# micro_RevA.net
KiCad netlist of a schematic drawn in EAGLE
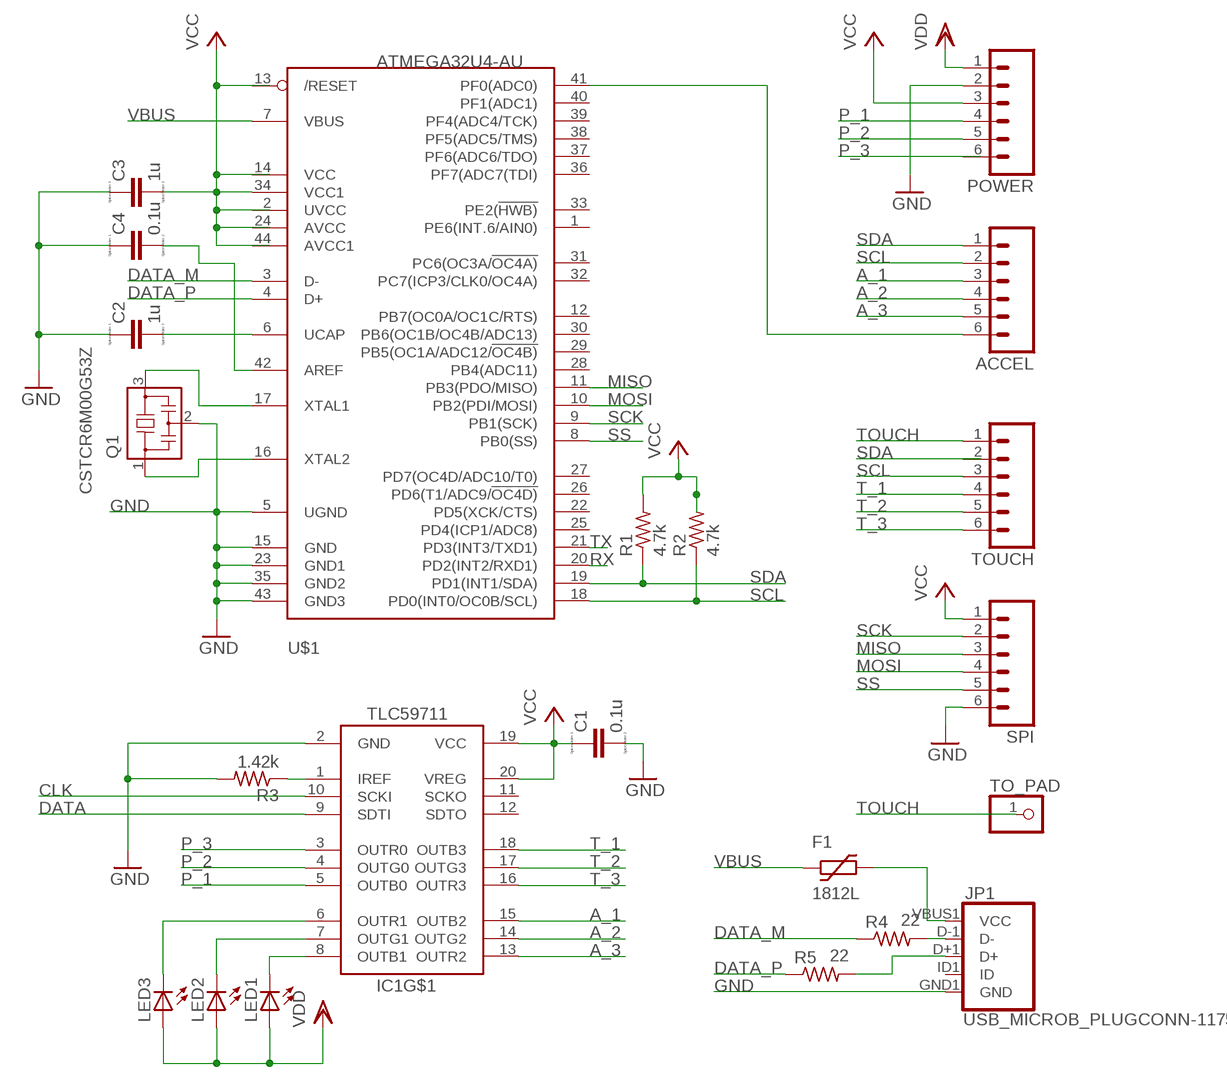
[diagram p0: schematic, sheet 1]

(export (version "E")
  (design (tool "Eeschema 10.0.6"))
  (components
    (comp (ref "ACCEL")
      (value "M06SMD-STRAIGHT-ALT")
      (footprint "eagle-import:1X06_SMD_STRAIGHT_ALT")
      (libsource (lib "eagle-import") (part "M06SMD-STRAIGHT-ALT"))
    )
    (comp (ref "C1")
      (value "0.1u")
      (footprint "eagle-import:C0603")
      (libsource (lib "eagle-import") (part "CC0603"))
    )
    (comp (ref "C2")
      (value "1u")
      (footprint "eagle-import:C0603")
      (libsource (lib "eagle-import") (part "CC0603"))
    )
    (comp (ref "C3")
      (value "1u")
      (footprint "eagle-import:C0603")
      (libsource (lib "eagle-import") (part "CC0603"))
    )
    (comp (ref "C4")
      (value "0.1u")
      (footprint "eagle-import:C0603")
      (libsource (lib "eagle-import") (part "CC0603"))
    )
    (comp (ref "F1")
      (value "1812L")
      (footprint "eagle-import:1812L")
      (libsource (lib "eagle-import") (part "1812L"))
    )
    (comp (ref "IC1")
      (value "TLC59711")
      (footprint "eagle-import:HTSSOP20DAP")
      (libsource (lib "eagle-import") (part "TLC59711"))
    )
    (comp (ref "JP1")
      (value "USB_MICROB_PLUGCONN-11752")
      (footprint "eagle-import:USB-B-MICRO-SMD_V03")
      (libsource (lib "eagle-import") (part "USB_MICROB_PLUGCONN-11752"))
    )
    (comp (ref "LED1")
      (value "LEDP-LCC-4")
      (footprint "eagle-import:P-LCC-4")
      (libsource (lib "eagle-import") (part "LEDP-LCC-4"))
    )
    (comp (ref "LED2")
      (value "LEDP-LCC-4")
      (footprint "eagle-import:P-LCC-4")
      (libsource (lib "eagle-import") (part "LEDP-LCC-4"))
    )
    (comp (ref "LED3")
      (value "LEDP-LCC-4")
      (footprint "eagle-import:P-LCC-4")
      (libsource (lib "eagle-import") (part "LEDP-LCC-4"))
    )
    (comp (ref "POWER")
      (value "M06SMD-STRAIGHT-ALT")
      (footprint "eagle-import:1X06_SMD_STRAIGHT_ALT")
      (libsource (lib "eagle-import") (part "M06SMD-STRAIGHT-ALT"))
    )
    (comp (ref "Q1")
      (value "CSTCR6M00G53Z")
      (footprint "eagle-import:CSTCR6M")
      (fields (field (name "MPN") "CSTCR6M00G53-R0"))
      (libsource (lib "eagle-import") (part "CSTCR6M00G53Z"))
    )
    (comp (ref "R1")
      (value "4.7k")
      (footprint "eagle-import:R0603")
      (libsource (lib "eagle-import") (part "R-US_R0603"))
    )
    (comp (ref "R2")
      (value "4.7k")
      (footprint "eagle-import:R0603")
      (libsource (lib "eagle-import") (part "R-US_R0603"))
    )
    (comp (ref "R3")
      (value "1.42k")
      (footprint "eagle-import:R0603")
      (libsource (lib "eagle-import") (part "R-US_R0603"))
    )
    (comp (ref "R4")
      (value "22")
      (footprint "eagle-import:R0603")
      (libsource (lib "eagle-import") (part "R-US_R0603"))
    )
    (comp (ref "R5")
      (value "22")
      (footprint "eagle-import:R0603")
      (libsource (lib "eagle-import") (part "R-US_R0603"))
    )
    (comp (ref "SPI")
      (value "M06SMD-STRAIGHT-ALT")
      (footprint "eagle-import:1X06_SMD_STRAIGHT_ALT")
      (libsource (lib "eagle-import") (part "M06SMD-STRAIGHT-ALT"))
    )
    (comp (ref "TOUCH")
      (value "M06SMD-STRAIGHT-ALT")
      (footprint "eagle-import:1X06_SMD_STRAIGHT_ALT")
      (libsource (lib "eagle-import") (part "M06SMD-STRAIGHT-ALT"))
    )
    (comp (ref "TO_PAD")
      (value "PINHD-1X1")
      (footprint "eagle-import:1X01")
      (libsource (lib "eagle-import") (part "PINHD-1X1"))
    )
    (comp (ref "U$1")
      (value "ATMEGA32U4-AU")
      (footprint "eagle-import:TQFP44")
      (libsource (lib "eagle-import") (part "ATMEGA32U4-AU"))
    )
  )
  (nets
    (net (code "1") (name "/A_1") (class "Default")
      (node (ref "ACCEL") (pin "3") (pinfunction "3_3") (pintype "passive"))
      (node (ref "IC1") (pin "15") (pinfunction "OUTB2_15") (pintype "open_collector"))
    )
    (net (code "2") (name "/A_2") (class "Default")
      (node (ref "ACCEL") (pin "4") (pinfunction "4_4") (pintype "passive"))
      (node (ref "IC1") (pin "14") (pinfunction "OUTG2_14") (pintype "open_collector"))
    )
    (net (code "3") (name "/A_3") (class "Default")
      (node (ref "ACCEL") (pin "5") (pinfunction "5_5") (pintype "passive"))
      (node (ref "IC1") (pin "13") (pinfunction "OUTR2_13") (pintype "open_collector"))
    )
    (net (code "4") (name "/CLK") (class "Default")
      (node (ref "IC1") (pin "10") (pinfunction "SCKI_10") (pintype "input"))
    )
    (net (code "5") (name "/DATA") (class "Default")
      (node (ref "IC1") (pin "9") (pinfunction "SDTI_9") (pintype "input"))
    )
    (net (code "6") (name "/DATA_M") (class "Default")
      (node (ref "R4") (pin "1") (pinfunction "1_1") (pintype "passive"))
      (node (ref "U$1") (pin "3") (pinfunction "D-_3") (pintype "bidirectional"))
    )
    (net (code "7") (name "/DATA_P") (class "Default")
      (node (ref "R5") (pin "1") (pinfunction "1_1") (pintype "passive"))
      (node (ref "U$1") (pin "4") (pinfunction "D+_4") (pintype "bidirectional"))
    )
    (net (code "8") (name "/MISO") (class "Default")
      (node (ref "SPI") (pin "3") (pinfunction "3_3") (pintype "passive"))
      (node (ref "U$1") (pin "11") (pinfunction "PB3(PDO/MISO)_11") (pintype "bidirectional"))
    )
    (net (code "9") (name "/MOSI") (class "Default")
      (node (ref "SPI") (pin "4") (pinfunction "4_4") (pintype "passive"))
      (node (ref "U$1") (pin "10") (pinfunction "PB2(PDI/MOSI)_10") (pintype "bidirectional"))
    )
    (net (code "10") (name "/P_1") (class "Default")
      (node (ref "IC1") (pin "5") (pinfunction "OUTB0_5") (pintype "open_collector"))
      (node (ref "POWER") (pin "4") (pinfunction "4_4") (pintype "passive"))
    )
    (net (code "11") (name "/P_2") (class "Default")
      (node (ref "IC1") (pin "4") (pinfunction "OUTG0_4") (pintype "open_collector"))
      (node (ref "POWER") (pin "5") (pinfunction "5_5") (pintype "passive"))
    )
    (net (code "12") (name "/P_3") (class "Default")
      (node (ref "IC1") (pin "3") (pinfunction "OUTR0_3") (pintype "open_collector"))
      (node (ref "POWER") (pin "6") (pinfunction "6_6") (pintype "passive"))
    )
    (net (code "13") (name "/RX") (class "Default")
      (node (ref "U$1") (pin "20") (pinfunction "PD2(INT2/RXD1)_20") (pintype "bidirectional"))
    )
    (net (code "14") (name "/SCK") (class "Default")
      (node (ref "SPI") (pin "2") (pinfunction "2_2") (pintype "passive"))
      (node (ref "U$1") (pin "9") (pinfunction "PB1(SCK)_9") (pintype "bidirectional"))
    )
    (net (code "15") (name "/SCL") (class "Default")
      (node (ref "ACCEL") (pin "2") (pinfunction "2_2") (pintype "passive"))
      (node (ref "R2") (pin "1") (pinfunction "1_1") (pintype "passive"))
      (node (ref "TOUCH") (pin "3") (pinfunction "3_3") (pintype "passive"))
      (node (ref "U$1") (pin "18") (pinfunction "PD0(INT0/OC0B/SCL)_18") (pintype "bidirectional"))
    )
    (net (code "16") (name "/SDA") (class "Default")
      (node (ref "ACCEL") (pin "1") (pinfunction "1_1") (pintype "passive"))
      (node (ref "R1") (pin "1") (pinfunction "1_1") (pintype "passive"))
      (node (ref "TOUCH") (pin "2") (pinfunction "2_2") (pintype "passive"))
      (node (ref "U$1") (pin "19") (pinfunction "PD1(INT1/SDA)_19") (pintype "bidirectional"))
    )
    (net (code "17") (name "/SS") (class "Default")
      (node (ref "SPI") (pin "5") (pinfunction "5_5") (pintype "passive"))
      (node (ref "U$1") (pin "8") (pinfunction "PB0(SS)_8") (pintype "bidirectional"))
    )
    (net (code "18") (name "/TOUCH") (class "Default")
      (node (ref "TOUCH") (pin "1") (pinfunction "1_1") (pintype "passive"))
      (node (ref "TO_PAD") (pin "1") (pinfunction "1_1") (pintype "passive"))
    )
    (net (code "19") (name "/TX") (class "Default")
      (node (ref "U$1") (pin "21") (pinfunction "PD3(INT3/TXD1)_21") (pintype "bidirectional"))
    )
    (net (code "20") (name "/T_1") (class "Default")
      (node (ref "IC1") (pin "18") (pinfunction "OUTB3_18") (pintype "open_collector"))
      (node (ref "TOUCH") (pin "4") (pinfunction "4_4") (pintype "passive"))
    )
    (net (code "21") (name "/T_2") (class "Default")
      (node (ref "IC1") (pin "17") (pinfunction "OUTG3_17") (pintype "open_collector"))
      (node (ref "TOUCH") (pin "5") (pinfunction "5_5") (pintype "passive"))
    )
    (net (code "22") (name "/T_3") (class "Default")
      (node (ref "IC1") (pin "16") (pinfunction "OUTR3_16") (pintype "open_collector"))
      (node (ref "TOUCH") (pin "6") (pinfunction "6_6") (pintype "passive"))
    )
    (net (code "23") (name "/VBUS") (class "Default")
      (node (ref "F1") (pin "P$1") (pinfunction "1_P$1") (pintype "passive"))
      (node (ref "U$1") (pin "7") (pinfunction "VBUS_7") (pintype "bidirectional"))
    )
    (net (code "24") (name "GND") (class "Default")
      (node (ref "C1") (pin "2") (pinfunction "2_2") (pintype "passive"))
      (node (ref "C2") (pin "1") (pinfunction "1_1") (pintype "passive"))
      (node (ref "C3") (pin "1") (pinfunction "1_1") (pintype "passive"))
      (node (ref "C4") (pin "1") (pinfunction "1_1") (pintype "passive"))
      (node (ref "IC1") (pin "2") (pinfunction "GND_2") (pintype "power_in"))
      (node (ref "JP1") (pin "GND1") (pinfunction "GND_GND1") (pintype "bidirectional"))
      (node (ref "POWER") (pin "2") (pinfunction "2_2") (pintype "passive"))
      (node (ref "Q1") (pin "2") (pinfunction "2_2") (pintype "passive"))
      (node (ref "R3") (pin "2") (pinfunction "2_2") (pintype "passive"))
      (node (ref "SPI") (pin "6") (pinfunction "6_6") (pintype "passive"))
      (node (ref "U$1") (pin "15") (pinfunction "GND_15") (pintype "bidirectional"))
      (node (ref "U$1") (pin "23") (pinfunction "GND1_23") (pintype "bidirectional"))
      (node (ref "U$1") (pin "35") (pinfunction "GND2_35") (pintype "bidirectional"))
      (node (ref "U$1") (pin "43") (pinfunction "GND3_43") (pintype "bidirectional"))
      (node (ref "U$1") (pin "5") (pinfunction "UGND_5") (pintype "bidirectional"))
    )
    (net (code "25") (name "Net-(F1-2)") (class "Default")
      (node (ref "F1") (pin "P$2") (pinfunction "2_P$2") (pintype "passive"))
      (node (ref "JP1") (pin "VBUS1") (pinfunction "VCC_VBUS1") (pintype "bidirectional"))
    )
    (net (code "26") (name "Net-(IC1A-IREF)") (class "Default")
      (node (ref "IC1") (pin "1") (pinfunction "IREF_1") (pintype "bidirectional"))
      (node (ref "R3") (pin "1") (pinfunction "1_1") (pintype "passive"))
    )
    (net (code "27") (name "Net-(IC1A-OUTB1)") (class "Default")
      (node (ref "IC1") (pin "8") (pinfunction "OUTB1_8") (pintype "open_collector"))
      (node (ref "LED1") (pin "C@4") (pinfunction "C_C@4") (pintype "passive"))
    )
    (net (code "28") (name "Net-(IC1A-OUTG1)") (class "Default")
      (node (ref "IC1") (pin "7") (pinfunction "OUTG1_7") (pintype "open_collector"))
      (node (ref "LED2") (pin "C@4") (pinfunction "C_C@4") (pintype "passive"))
    )
    (net (code "29") (name "Net-(IC1A-OUTR1)") (class "Default")
      (node (ref "IC1") (pin "6") (pinfunction "OUTR1_6") (pintype "open_collector"))
      (node (ref "LED3") (pin "C@4") (pinfunction "C_C@4") (pintype "passive"))
    )
    (net (code "30") (name "Net-(JP1-D+)") (class "Default")
      (node (ref "JP1") (pin "D+1") (pinfunction "D+_D+1") (pintype "bidirectional"))
      (node (ref "R5") (pin "2") (pinfunction "2_2") (pintype "passive"))
    )
    (net (code "31") (name "Net-(JP1-D-)") (class "Default")
      (node (ref "JP1") (pin "D-1") (pinfunction "D-_D-1") (pintype "bidirectional"))
      (node (ref "R4") (pin "2") (pinfunction "2_2") (pintype "passive"))
    )
    (net (code "32") (name "Net-(U$1-AREF)") (class "Default")
      (node (ref "C4") (pin "2") (pinfunction "2_2") (pintype "passive"))
      (node (ref "U$1") (pin "42") (pinfunction "AREF_42") (pintype "bidirectional"))
    )
    (net (code "33") (name "Net-(U$1-PF0(ADC0))") (class "Default")
      (node (ref "ACCEL") (pin "6") (pinfunction "6_6") (pintype "passive"))
      (node (ref "U$1") (pin "41") (pinfunction "PF0(ADC0)_41") (pintype "bidirectional"))
    )
    (net (code "34") (name "Net-(U$1-UCAP)") (class "Default")
      (node (ref "C2") (pin "2") (pinfunction "2_2") (pintype "passive"))
      (node (ref "U$1") (pin "6") (pinfunction "UCAP_6") (pintype "bidirectional"))
    )
    (net (code "35") (name "Net-(U$1-XTAL1)") (class "Default")
      (node (ref "Q1") (pin "3") (pinfunction "3_3") (pintype "passive"))
      (node (ref "U$1") (pin "17") (pinfunction "XTAL1_17") (pintype "bidirectional"))
    )
    (net (code "36") (name "Net-(U$1-XTAL2)") (class "Default")
      (node (ref "Q1") (pin "1") (pinfunction "1_1") (pintype "passive"))
      (node (ref "U$1") (pin "16") (pinfunction "XTAL2_16") (pintype "bidirectional"))
    )
    (net (code "37") (name "VCC") (class "Default")
      (node (ref "C1") (pin "1") (pinfunction "1_1") (pintype "passive"))
      (node (ref "C3") (pin "2") (pinfunction "2_2") (pintype "passive"))
      (node (ref "IC1") (pin "19") (pinfunction "VCC_19") (pintype "power_in"))
      (node (ref "IC1") (pin "20") (pinfunction "VREG_20") (pintype "bidirectional"))
      (node (ref "POWER") (pin "3") (pinfunction "3_3") (pintype "passive"))
      (node (ref "R1") (pin "2") (pinfunction "2_2") (pintype "passive"))
      (node (ref "R2") (pin "2") (pinfunction "2_2") (pintype "passive"))
      (node (ref "SPI") (pin "1") (pinfunction "1_1") (pintype "passive"))
      (node (ref "U$1") (pin "34") (pinfunction "VCC1_34") (pintype "bidirectional"))
    )
    (net (code "38") (name "VDD") (class "Default")
      (node (ref "LED1") (pin "A") (pinfunction "A_A") (pintype "passive"))
      (node (ref "LED2") (pin "A") (pinfunction "A_A") (pintype "passive"))
      (node (ref "LED3") (pin "A") (pinfunction "A_A") (pintype "passive"))
      (node (ref "POWER") (pin "1") (pinfunction "1_1") (pintype "passive"))
    )
    (net (code "39") (name "unconnected-(IC1A-SCKO-Pad11)") (class "Default")
      (node (ref "IC1") (pin "11") (pinfunction "SCKO_11") (pintype "output"))
    )
    (net (code "40") (name "unconnected-(IC1A-SDTO-Pad12)") (class "Default")
      (node (ref "IC1") (pin "12") (pinfunction "SDTO_12") (pintype "output"))
    )
    (net (code "41") (name "unconnected-(JP1-ID-PadID1)") (class "Default")
      (node (ref "JP1") (pin "ID1") (pinfunction "ID_ID1") (pintype "bidirectional"))
    )
    (net (code "42") (name "unconnected-(U$1-AVCC-Pad24)") (class "Default")
      (node (ref "U$1") (pin "24") (pinfunction "AVCC_24") (pintype "bidirectional"))
    )
    (net (code "43") (name "unconnected-(U$1-AVCC1-Pad44)") (class "Default")
      (node (ref "U$1") (pin "44") (pinfunction "AVCC1_44") (pintype "bidirectional"))
    )
    (net (code "44") (name "unconnected-(U$1-PB4(ADC11)-Pad28)") (class "Default")
      (node (ref "U$1") (pin "28") (pinfunction "PB4(ADC11)_28") (pintype "bidirectional"))
    )
    (net (code "45") (name "unconnected-(U$1-PB5(OC1A{slash}ADC12{slash}~{OC4B})-Pad29)") (class "Default")
      (node (ref "U$1") (pin "29") (pinfunction "PB5(OC1A/ADC12/~{OC4B})_29") (pintype "bidirectional"))
    )
    (net (code "46") (name "unconnected-(U$1-PB6(OC1B{slash}OC4B{slash}ADC13)-Pad30)") (class "Default")
      (node (ref "U$1") (pin "30") (pinfunction "PB6(OC1B/OC4B/ADC13)_30") (pintype "bidirectional"))
    )
    (net (code "47") (name "unconnected-(U$1-PB7(OC0A{slash}OC1C{slash}RTS)-Pad12)") (class "Default")
      (node (ref "U$1") (pin "12") (pinfunction "PB7(OC0A/OC1C/RTS)_12") (pintype "bidirectional"))
    )
    (net (code "48") (name "unconnected-(U$1-PC6(OC3A{slash}~{OC4A})-Pad31)") (class "Default")
      (node (ref "U$1") (pin "31") (pinfunction "PC6(OC3A/~{OC4A})_31") (pintype "bidirectional"))
    )
    (net (code "49") (name "unconnected-(U$1-PC7(ICP3{slash}CLK0{slash}OC4A)-Pad32)") (class "Default")
      (node (ref "U$1") (pin "32") (pinfunction "PC7(ICP3/CLK0/OC4A)_32") (pintype "bidirectional"))
    )
    (net (code "50") (name "unconnected-(U$1-PD4(ICP1{slash}ADC8)-Pad25)") (class "Default")
      (node (ref "U$1") (pin "25") (pinfunction "PD4(ICP1/ADC8)_25") (pintype "bidirectional"))
    )
    (net (code "51") (name "unconnected-(U$1-PD5(XCK{slash}CTS)-Pad22)") (class "Default")
      (node (ref "U$1") (pin "22") (pinfunction "PD5(XCK/CTS)_22") (pintype "bidirectional"))
    )
    (net (code "52") (name "unconnected-(U$1-PD6(T1{slash}ADC9{slash}~{OC4D})-Pad26)") (class "Default")
      (node (ref "U$1") (pin "26") (pinfunction "PD6(T1/ADC9/~{OC4D})_26") (pintype "bidirectional"))
    )
    (net (code "53") (name "unconnected-(U$1-PD7(OC4D{slash}ADC10{slash}T0)-Pad27)") (class "Default")
      (node (ref "U$1") (pin "27") (pinfunction "PD7(OC4D/ADC10/T0)_27") (pintype "bidirectional"))
    )
    (net (code "54") (name "unconnected-(U$1-PE2(~{HWB})-Pad33)") (class "Default")
      (node (ref "U$1") (pin "33") (pinfunction "PE2(~{HWB})_33") (pintype "bidirectional"))
    )
    (net (code "55") (name "unconnected-(U$1-PE6(INT.6{slash}AIN0)-Pad1)") (class "Default")
      (node (ref "U$1") (pin "1") (pinfunction "PE6(INT.6/AIN0)_1") (pintype "bidirectional"))
    )
    (net (code "56") (name "unconnected-(U$1-PF1(ADC1)-Pad40)") (class "Default")
      (node (ref "U$1") (pin "40") (pinfunction "PF1(ADC1)_40") (pintype "bidirectional"))
    )
    (net (code "57") (name "unconnected-(U$1-PF4(ADC4{slash}TCK)-Pad39)") (class "Default")
      (node (ref "U$1") (pin "39") (pinfunction "PF4(ADC4/TCK)_39") (pintype "bidirectional"))
    )
    (net (code "58") (name "unconnected-(U$1-PF5(ADC5{slash}TMS)-Pad38)") (class "Default")
      (node (ref "U$1") (pin "38") (pinfunction "PF5(ADC5/TMS)_38") (pintype "bidirectional"))
    )
    (net (code "59") (name "unconnected-(U$1-PF6(ADC6{slash}TDO)-Pad37)") (class "Default")
      (node (ref "U$1") (pin "37") (pinfunction "PF6(ADC6/TDO)_37") (pintype "bidirectional"))
    )
    (net (code "60") (name "unconnected-(U$1-PF7(ADC7(TDI)-Pad36)") (class "Default")
      (node (ref "U$1") (pin "36") (pinfunction "PF7(ADC7(TDI)_36") (pintype "bidirectional"))
    )
    (net (code "61") (name "unconnected-(U$1-UVCC-Pad2)") (class "Default")
      (node (ref "U$1") (pin "2") (pinfunction "UVCC_2") (pintype "bidirectional"))
    )
    (net (code "62") (name "unconnected-(U$1-VCC-Pad14)") (class "Default")
      (node (ref "U$1") (pin "14") (pinfunction "VCC_14") (pintype "bidirectional"))
    )
    (net (code "63") (name "unconnected-(U$1-{slash}RESET-Pad13)") (class "Default")
      (node (ref "U$1") (pin "13") (pinfunction "/RESET_13") (pintype "bidirectional"))
    )
  )
)
